# Power_Regulators_Digital_3.net
KiCad netlist of a schematic drawn in Altium Designer
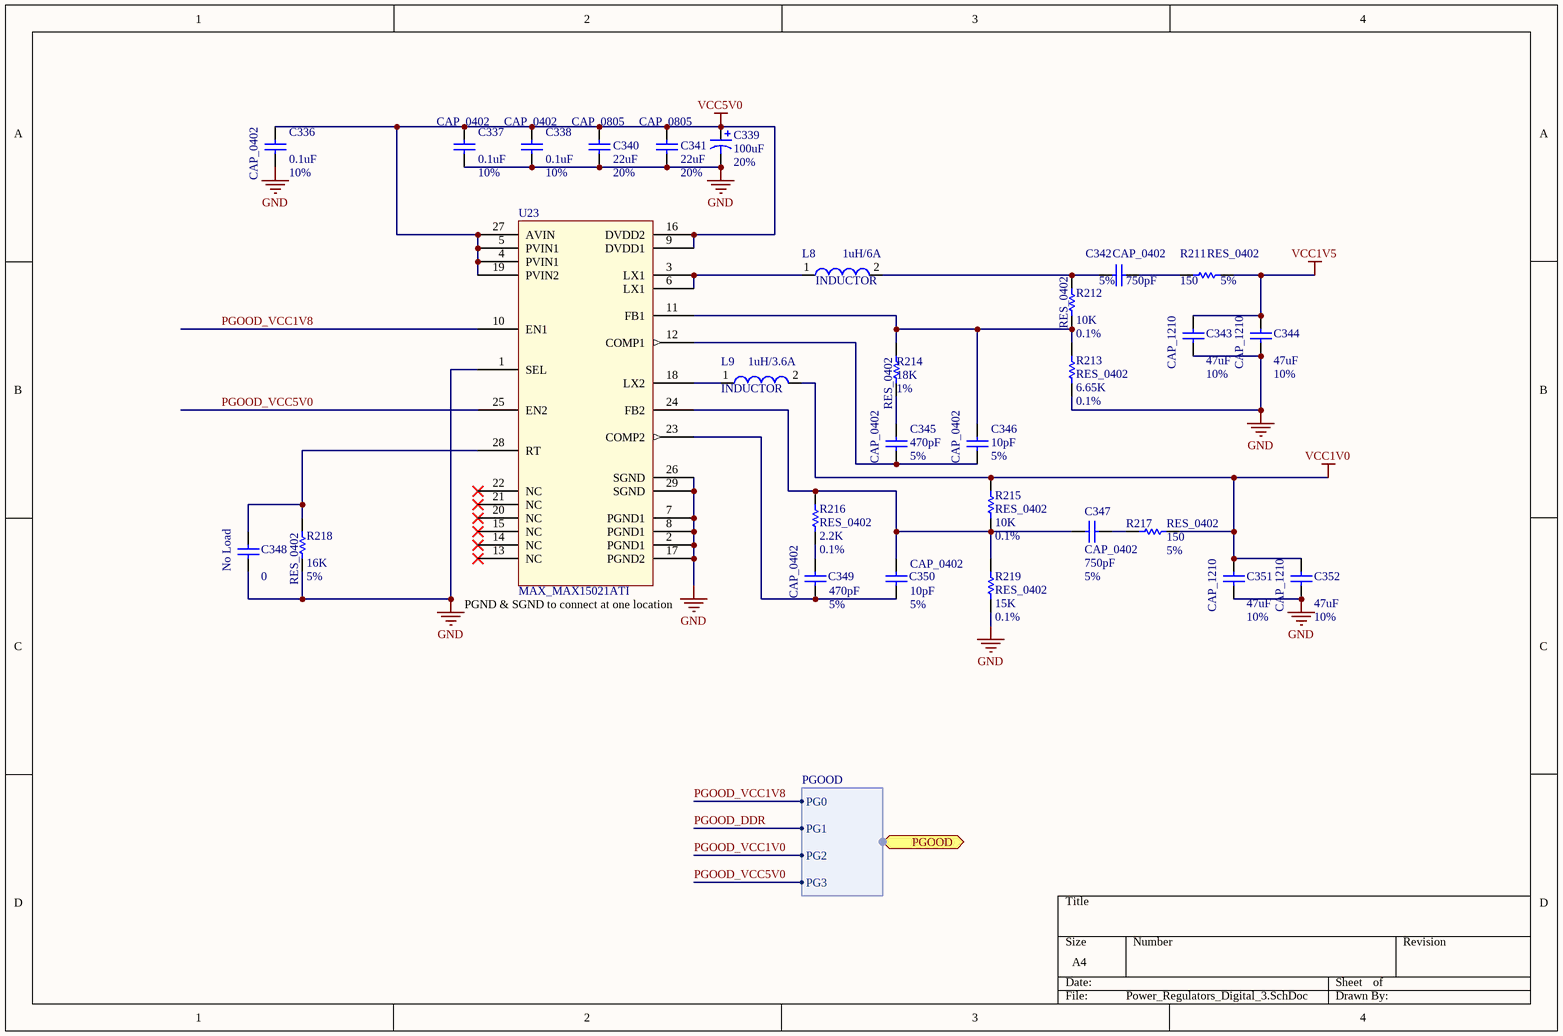
[diagram p0: Power_Regulators_Digital_3.SchDoc]

(export (version "E")
  (design (tool "Eeschema 10.0.6"))
  (components
    (comp (ref "C336")
      (value "CAP_0402")
      (footprint "CAPC0402(1005)60_N")
      (description "0.1uf, ceramic, 10%, 6.3V, X5R, 0402")
      (fields
        (field (name "ALTIUM_VALUE") "0.1uF")
        (field (name "TOLERANCE") "10%")
        (field (name "PART NUMBER") "C1005X5R0J104K")
        (field (name "MANUFACTURER") "TDK Corporation")
      )
      (libsource (lib "COMRAD_Database") (part "CAP_0402"))
    )
    (comp (ref "C337")
      (value "CAP_0402")
      (footprint "CAPC0402(1005)60_N")
      (description "0.1uf, ceramic, 10%, 6.3V, X5R, 0402")
      (fields
        (field (name "ALTIUM_VALUE") "0.1uF")
        (field (name "TOLERANCE") "10%")
        (field (name "PART NUMBER") "C1005X5R0J104K")
        (field (name "MANUFACTURER") "TDK Corporation")
      )
      (libsource (lib "COMRAD_Database") (part "CAP_0402"))
    )
    (comp (ref "C338")
      (value "CAP_0402")
      (footprint "CAPC0402(1005)60_N")
      (description "0.1uf, ceramic, 10%, 6.3V, X5R, 0402")
      (fields
        (field (name "ALTIUM_VALUE") "0.1uF")
        (field (name "TOLERANCE") "10%")
        (field (name "PART NUMBER") "C1005X5R0J104K")
        (field (name "MANUFACTURER") "TDK Corporation")
      )
      (libsource (lib "COMRAD_Database") (part "CAP_0402"))
    )
    (comp (ref "C339")
      (value "100uF")
      (footprint "Polarized_CAPC1210(3225)")
      (description "100uF, tantalum, 20% 10V, 1210")
      (fields
        (field (name "TOLERANCE") "20%")
        (field (name "PART NUMBER") "TLCT107M010XTA")
        (field (name "MANUFACTURER") "AVX Corporation")
      )
      (libsource (lib "COMRAD_Database") (part "Cap Pol1"))
    )
    (comp (ref "C340")
      (value "CAP_0805")
      (footprint "CAPC0805(2012)75_N")
      (description "22uF, ceramic, 20%, 6.3V, X5R, 0805")
      (fields
        (field (name "ALTIUM_VALUE") "22uF")
        (field (name "TOLERANCE") "20%")
        (field (name "PART NUMBER") "JMK212BJ226MG-T")
        (field (name "MANUFACTURER") "Taiyo Yuden")
      )
      (libsource (lib "COMRAD_Database") (part "CAP_0805"))
    )
    (comp (ref "C341")
      (value "CAP_0805")
      (footprint "CAPC0805(2012)75_N")
      (description "22uF, ceramic, 20%, 6.3V, X5R, 0805")
      (fields
        (field (name "ALTIUM_VALUE") "22uF")
        (field (name "TOLERANCE") "20%")
        (field (name "PART NUMBER") "JMK212BJ226MG-T")
        (field (name "MANUFACTURER") "Taiyo Yuden")
      )
      (libsource (lib "COMRAD_Database") (part "CAP_0805"))
    )
    (comp (ref "C342")
      (value "CAP_0402")
      (footprint "CAPC0402(1005)60_N")
      (description "750pF, ceramic, 5% 25V NP0, 0402")
      (fields
        (field (name "ALTIUM_VALUE") "750pF")
        (field (name "TOLERANCE") "5%")
        (field (name "PART NUMBER") "C0402C751J3GACTU")
        (field (name "MANUFACTURER") "Kemet")
      )
      (libsource (lib "COMRAD_Database") (part "CAP_0402"))
    )
    (comp (ref "C343")
      (value "CAP_1210")
      (footprint "CAPC1210(3225)100_N")
      (description "47uF, ceramic 10% 10V, X5R, 1210")
      (fields
        (field (name "ALTIUM_VALUE") "47uF")
        (field (name "TOLERANCE") "10%")
        (field (name "PART NUMBER") "GRM32ER61A476KE20L")
        (field (name "MANUFACTURER") "Murata Electronics North America")
      )
      (libsource (lib "COMRAD_Database") (part "CAP_1210"))
    )
    (comp (ref "C344")
      (value "CAP_1210")
      (footprint "CAPC1210(3225)100_N")
      (description "47uF, ceramic 10% 10V, X5R, 1210")
      (fields
        (field (name "ALTIUM_VALUE") "47uF")
        (field (name "TOLERANCE") "10%")
        (field (name "PART NUMBER") "GRM32ER61A476KE20L")
        (field (name "MANUFACTURER") "Murata Electronics North America")
      )
      (libsource (lib "COMRAD_Database") (part "CAP_1210"))
    )
    (comp (ref "C345")
      (value "CAP_0402")
      (footprint "CAPC0402(1005)60_N")
      (description "470pF, ceramic, 5%, 25V, X7R, 0402")
      (fields
        (field (name "ALTIUM_VALUE") "470pF")
        (field (name "TOLERANCE") "5%")
        (field (name "PART NUMBER") "ECJ-0EB1E471K")
        (field (name "MANUFACTURER") "Panasonic-ECG")
      )
      (libsource (lib "COMRAD_Database") (part "CAP_0402"))
    )
    (comp (ref "C346")
      (value "CAP_0402")
      (footprint "CAPC0402(1005)60_N")
      (description "10pF, ceramic, 5%, 50V, NP0, 0402")
      (fields
        (field (name "ALTIUM_VALUE") "10pF")
        (field (name "TOLERANCE") "5%")
        (field (name "PART NUMBER") "VJ0402A100JXACW1BC")
        (field (name "MANUFACTURER") "BC COMPONENTS")
      )
      (libsource (lib "COMRAD_Database") (part "CAP_0402"))
    )
    (comp (ref "C347")
      (value "CAP_0402")
      (footprint "CAPC0402(1005)60_N")
      (description "750pF, ceramic, 5% 25V NP0, 0402")
      (fields
        (field (name "ALTIUM_VALUE") "750pF")
        (field (name "TOLERANCE") "5%")
        (field (name "PART NUMBER") "C0402C751J3GACTU")
        (field (name "MANUFACTURER") "Kemet")
      )
      (libsource (lib "COMRAD_Database") (part "CAP_0402"))
    )
    (comp (ref "C348")
      (value "0")
      (footprint "CAPC0201(0603)33_N:CAPC0201(0603)33_N")
      (description "Generic Capacitor")
      (fields
        (field (name "PART NUMBER") "No Load_0")
        (field (name "MANUFACTURER") "No Load")
        (field (name "Comment") "CAP_0201")
      )
      (libsource (lib "COMRAD_Database") (part "CAP_0201"))
    )
    (comp (ref "C349")
      (value "CAP_0402")
      (footprint "CAPC0402(1005)60_N")
      (description "470pF, ceramic, 5%, 25V, X7R, 0402")
      (fields
        (field (name "ALTIUM_VALUE") "470pF")
        (field (name "TOLERANCE") "5%")
        (field (name "PART NUMBER") "ECJ-0EB1E471K")
        (field (name "MANUFACTURER") "Panasonic-ECG")
      )
      (libsource (lib "COMRAD_Database") (part "CAP_0402"))
    )
    (comp (ref "C350")
      (value "CAP_0402")
      (footprint "CAPC0402(1005)60_N")
      (description "10pF, ceramic, 5%, 50V, NP0, 0402")
      (fields
        (field (name "ALTIUM_VALUE") "10pF")
        (field (name "TOLERANCE") "5%")
        (field (name "PART NUMBER") "VJ0402A100JXACW1BC")
        (field (name "MANUFACTURER") "BC COMPONENTS")
      )
      (libsource (lib "COMRAD_Database") (part "CAP_0402"))
    )
    (comp (ref "C351")
      (value "CAP_1210")
      (footprint "CAPC1210(3225)100_N")
      (description "47uF, ceramic 10% 10V, X5R, 1210")
      (fields
        (field (name "ALTIUM_VALUE") "47uF")
        (field (name "TOLERANCE") "10%")
        (field (name "PART NUMBER") "GRM32ER61A476KE20L")
        (field (name "MANUFACTURER") "Murata Electronics North America")
      )
      (libsource (lib "COMRAD_Database") (part "CAP_1210"))
    )
    (comp (ref "C352")
      (value "CAP_1210")
      (footprint "CAPC1210(3225)100_N")
      (description "47uF, ceramic 10% 10V, X5R, 1210")
      (fields
        (field (name "ALTIUM_VALUE") "47uF")
        (field (name "TOLERANCE") "10%")
        (field (name "PART NUMBER") "GRM32ER61A476KE20L")
        (field (name "MANUFACTURER") "Murata Electronics North America")
      )
      (libsource (lib "COMRAD_Database") (part "CAP_1210"))
    )
    (comp (ref "L8")
      (value "INDUCTOR")
      (footprint "Inductor_SRN6045-Series_2-PIN")
      (description "SRN6045-1R0Y, 1uH 4.2A-8.5A, CDRH6D38")
      (fields
        (field (name "ALTIUM_VALUE") "1uH/6A")
        (field (name "PART NUMBER") "SRN6045-1R0Y")
        (field (name "MANUFACTURER") "Bourns")
      )
      (libsource (lib "COMRAD_Database") (part "INDUCTOR"))
    )
    (comp (ref "L9")
      (value "INDUCTOR")
      (footprint "Inductor_NRS5020T1R0NMGJ_2-PIN")
      (description "NRS5020T1R0NMGJ, 1uH 3.6A, 5020")
      (fields
        (field (name "ALTIUM_VALUE") "1uH/3.6A")
        (field (name "PART NUMBER") "NRS5020T1R0NMGJ")
        (field (name "MANUFACTURER") "Taiyo Yuden")
      )
      (libsource (lib "COMRAD_Database") (part "INDUCTOR"))
    )
    (comp (ref "R211")
      (value "RES_0402")
      (footprint "RESC0402(1005)_N")
      (description "150 ohm, 5% 1/16W, 0402")
      (fields
        (field (name "ALTIUM_VALUE") "150")
        (field (name "TOLERANCE") "5%")
        (field (name "PART NUMBER") "RC0402JR-07150RL")
        (field (name "MANUFACTURER") "Yageo America")
      )
      (libsource (lib "COMRAD_Database") (part "RES_0402"))
    )
    (comp (ref "R212")
      (value "RES_0402")
      (footprint "RESC0402(1005)_N")
      (description "10K ohm, 0.1% 1/16W, 0402")
      (fields
        (field (name "ALTIUM_VALUE") "10K")
        (field (name "TOLERANCE") "0.1%")
        (field (name "PART NUMBER") "ERA-2AEB103X")
        (field (name "MANUFACTURER") "Panasonic - ECG")
      )
      (libsource (lib "COMRAD_Database") (part "RES_0402"))
    )
    (comp (ref "R213")
      (value "RES_0402")
      (footprint "RESC0402(1005)_N")
      (description "6.65K ohm, 0.1% 1/16W, 0402")
      (fields
        (field (name "ALTIUM_VALUE") "6.65K")
        (field (name "TOLERANCE") "0.1%")
        (field (name "PART NUMBER") "2-1879215-2")
        (field (name "MANUFACTURER") "TE Connectivity")
      )
      (libsource (lib "COMRAD_Database") (part "RES_0402"))
    )
    (comp (ref "R214")
      (value "RES_0402")
      (footprint "RESC0402(1005)_N")
      (description "18K ohm, 1% 1/16W, 0402")
      (fields
        (field (name "ALTIUM_VALUE") "18K")
        (field (name "TOLERANCE") "1%")
        (field (name "PART NUMBER") "MCR01MZPF1802")
        (field (name "MANUFACTURER") "ROHM")
      )
      (libsource (lib "COMRAD_Database") (part "RES_0402"))
    )
    (comp (ref "R215")
      (value "RES_0402")
      (footprint "RESC0402(1005)_N")
      (description "10K ohm, 0.1% 1/16W, 0402")
      (fields
        (field (name "ALTIUM_VALUE") "10K")
        (field (name "TOLERANCE") "0.1%")
        (field (name "PART NUMBER") "ERA-2AEB103X")
        (field (name "MANUFACTURER") "Panasonic - ECG")
      )
      (libsource (lib "COMRAD_Database") (part "RES_0402"))
    )
    (comp (ref "R216")
      (value "RES_0402")
      (footprint "RESC0402(1005)_N")
      (description "2.2K ohm, 0.1% 1/16W, 0402")
      (fields
        (field (name "ALTIUM_VALUE") "2.2K")
        (field (name "TOLERANCE") "0.1%")
        (field (name "PART NUMBER") "ERA-2AEB222X")
        (field (name "MANUFACTURER") "Panasonic - ECG")
      )
      (libsource (lib "COMRAD_Database") (part "RES_0402"))
    )
    (comp (ref "R217")
      (value "RES_0402")
      (footprint "RESC0402(1005)_N")
      (description "150 ohm, 5% 1/16W, 0402")
      (fields
        (field (name "ALTIUM_VALUE") "150")
        (field (name "TOLERANCE") "5%")
        (field (name "PART NUMBER") "RC0402JR-07150RL")
        (field (name "MANUFACTURER") "Yageo America")
      )
      (libsource (lib "COMRAD_Database") (part "RES_0402"))
    )
    (comp (ref "R218")
      (value "RES_0402")
      (footprint "RESC0402(1005)_N")
      (description "16K ohm, 5% 1/16W, 0402")
      (fields
        (field (name "ALTIUM_VALUE") "16K")
        (field (name "TOLERANCE") "5%")
        (field (name "PART NUMBER") "CRCW040216K0JNED")
        (field (name "MANUFACTURER") "Vishay/Dale")
      )
      (libsource (lib "COMRAD_Database") (part "RES_0402"))
    )
    (comp (ref "R219")
      (value "RES_0402")
      (footprint "RESC0402(1005)_N")
      (description "15K ohm, 0.1% 1/16W, 0402")
      (fields
        (field (name "ALTIUM_VALUE") "15K")
        (field (name "TOLERANCE") "0.1%")
        (field (name "PART NUMBER") "ERA-2AEB153X")
        (field (name "MANUFACTURER") "Panasonic - ECG")
      )
      (libsource (lib "COMRAD_Database") (part "RES_0402"))
    )
    (comp (ref "U23")
      (value "MAX_MAX15021ATI")
      (footprint "MAX_MAX15021ATI_28TQFN_T2855-6")
      (description "MAX15021ATI, 4A/2A, 4MHz, Step-Down DC-DC Regulator, TQFN28")
      (fields
        (field (name "PART NUMBER") "MAX15021ATI+")
        (field (name "MANUFACTURER") "Maxim Integrated Products")
      )
      (libsource (lib "COMRAD_Database") (part "MAX_MAX15021ATI"))
    )
  )
  (nets
    (net (code "4") (name "/PGOOD_VCC1V8") (class "Default")
      (node (ref "U23") (pin "10") (pinfunction "EN1_10") (pintype "power_in"))
    )
    (net (code "5") (name "/PGOOD_VCC5V0") (class "Default")
      (node (ref "U23") (pin "25") (pinfunction "EN2_25") (pintype "power_in"))
    )
    (net (code "7") (name "GND") (class "Default")
      (node (ref "C336") (pin "1") (pinfunction "1_1") (pintype "passive"))
      (node (ref "C337") (pin "1") (pinfunction "1_1") (pintype "passive"))
      (node (ref "C338") (pin "1") (pinfunction "1_1") (pintype "passive"))
      (node (ref "C339") (pin "2") (pinfunction "2_2") (pintype "passive"))
      (node (ref "C340") (pin "1") (pinfunction "1_1") (pintype "passive"))
      (node (ref "C341") (pin "1") (pinfunction "1_1") (pintype "passive"))
      (node (ref "C343") (pin "1") (pinfunction "1_1") (pintype "passive"))
      (node (ref "C344") (pin "1") (pinfunction "1_1") (pintype "passive"))
      (node (ref "C348") (pin "1") (pinfunction "1_1") (pintype "passive"))
      (node (ref "C351") (pin "1") (pinfunction "1_1") (pintype "passive"))
      (node (ref "C352") (pin "1") (pinfunction "1_1") (pintype "passive"))
      (node (ref "R213") (pin "1") (pinfunction "1_1") (pintype "passive"))
      (node (ref "R218") (pin "2") (pinfunction "2_2") (pintype "passive"))
      (node (ref "R219") (pin "1") (pinfunction "1_1") (pintype "passive"))
      (node (ref "U23") (pin "1") (pinfunction "SEL_1") (pintype "power_in"))
      (node (ref "U23") (pin "17") (pinfunction "PGND2_17") (pintype "power_in"))
      (node (ref "U23") (pin "2") (pinfunction "PGND1_2") (pintype "power_in"))
      (node (ref "U23") (pin "26") (pinfunction "SGND_26") (pintype "power_in"))
      (node (ref "U23") (pin "29") (pinfunction "SGND_29") (pintype "power_in"))
      (node (ref "U23") (pin "7") (pinfunction "PGND1_7") (pintype "power_in"))
      (node (ref "U23") (pin "8") (pinfunction "PGND1_8") (pintype "power_in"))
    )
    (net (code "8") (name "Net-(C342-Pad1)") (class "Default")
      (node (ref "C342") (pin "1") (pinfunction "1_1") (pintype "passive"))
      (node (ref "L8") (pin "2") (pinfunction "2_2") (pintype "passive"))
      (node (ref "R212") (pin "2") (pinfunction "2_2") (pintype "passive"))
    )
    (net (code "9") (name "Net-(C342-Pad2)") (class "Default")
      (node (ref "C342") (pin "2") (pinfunction "2_2") (pintype "passive"))
      (node (ref "R211") (pin "1") (pinfunction "1_1") (pintype "passive"))
    )
    (net (code "10") (name "Net-(C345-Pad2)") (class "Default")
      (node (ref "C345") (pin "2") (pinfunction "2_2") (pintype "passive"))
      (node (ref "R214") (pin "1") (pinfunction "1_1") (pintype "passive"))
    )
    (net (code "11") (name "Net-(C347-Pad2)") (class "Default")
      (node (ref "C347") (pin "2") (pinfunction "2_2") (pintype "passive"))
      (node (ref "R217") (pin "1") (pinfunction "1_1") (pintype "passive"))
    )
    (net (code "12") (name "Net-(C349-Pad2)") (class "Default")
      (node (ref "C349") (pin "2") (pinfunction "2_2") (pintype "passive"))
      (node (ref "R216") (pin "1") (pinfunction "1_1") (pintype "passive"))
    )
    (net (code "13") (name "Net-(L8-Pad1)") (class "Default")
      (node (ref "L8") (pin "1") (pinfunction "1_1") (pintype "passive"))
      (node (ref "U23") (pin "3") (pinfunction "LX1_3") (pintype "power_in"))
      (node (ref "U23") (pin "6") (pinfunction "LX1_6") (pintype "power_in"))
    )
    (net (code "14") (name "Net-(U23-COMP1)") (class "Default")
      (node (ref "C345") (pin "1") (pinfunction "1_1") (pintype "passive"))
      (node (ref "C346") (pin "1") (pinfunction "1_1") (pintype "passive"))
      (node (ref "U23") (pin "12") (pinfunction "COMP1_12") (pintype "output"))
    )
    (net (code "15") (name "Net-(U23-COMP2)") (class "Default")
      (node (ref "C349") (pin "1") (pinfunction "1_1") (pintype "passive"))
      (node (ref "C350") (pin "1") (pinfunction "1_1") (pintype "passive"))
      (node (ref "U23") (pin "23") (pinfunction "COMP2_23") (pintype "output"))
    )
    (net (code "16") (name "Net-(U23-FB1)") (class "Default")
      (node (ref "C346") (pin "2") (pinfunction "2_2") (pintype "passive"))
      (node (ref "R212") (pin "1") (pinfunction "1_1") (pintype "passive"))
      (node (ref "R213") (pin "2") (pinfunction "2_2") (pintype "passive"))
      (node (ref "R214") (pin "2") (pinfunction "2_2") (pintype "passive"))
      (node (ref "U23") (pin "11") (pinfunction "FB1_11") (pintype "power_in"))
    )
    (net (code "17") (name "Net-(U23-FB2)") (class "Default")
      (node (ref "C347") (pin "1") (pinfunction "1_1") (pintype "passive"))
      (node (ref "C350") (pin "2") (pinfunction "2_2") (pintype "passive"))
      (node (ref "R215") (pin "1") (pinfunction "1_1") (pintype "passive"))
      (node (ref "R216") (pin "2") (pinfunction "2_2") (pintype "passive"))
      (node (ref "R219") (pin "2") (pinfunction "2_2") (pintype "passive"))
      (node (ref "U23") (pin "24") (pinfunction "FB2_24") (pintype "power_in"))
    )
    (net (code "18") (name "Net-(U23-LX2)") (class "Default")
      (node (ref "L9") (pin "1") (pinfunction "1_1") (pintype "passive"))
      (node (ref "U23") (pin "18") (pinfunction "LX2_18") (pintype "power_in"))
    )
    (net (code "19") (name "Net-(U23-RT)") (class "Default")
      (node (ref "C348") (pin "2") (pinfunction "2_2") (pintype "passive"))
      (node (ref "R218") (pin "1") (pinfunction "1_1") (pintype "passive"))
      (node (ref "U23") (pin "28") (pinfunction "RT_28") (pintype "power_in"))
    )
    (net (code "20") (name "VCC1V0") (class "Default")
      (node (ref "C351") (pin "2") (pinfunction "2_2") (pintype "passive"))
      (node (ref "C352") (pin "2") (pinfunction "2_2") (pintype "passive"))
      (node (ref "L9") (pin "2") (pinfunction "2_2") (pintype "passive"))
      (node (ref "R215") (pin "2") (pinfunction "2_2") (pintype "passive"))
      (node (ref "R217") (pin "2") (pinfunction "2_2") (pintype "passive"))
    )
    (net (code "21") (name "VCC1V5") (class "Default")
      (node (ref "C343") (pin "2") (pinfunction "2_2") (pintype "passive"))
      (node (ref "C344") (pin "2") (pinfunction "2_2") (pintype "passive"))
      (node (ref "R211") (pin "2") (pinfunction "2_2") (pintype "passive"))
    )
    (net (code "22") (name "VCC5V0") (class "Default")
      (node (ref "C336") (pin "2") (pinfunction "2_2") (pintype "passive"))
      (node (ref "C337") (pin "2") (pinfunction "2_2") (pintype "passive"))
      (node (ref "C338") (pin "2") (pinfunction "2_2") (pintype "passive"))
      (node (ref "C339") (pin "1") (pinfunction "1_1") (pintype "passive"))
      (node (ref "C340") (pin "2") (pinfunction "2_2") (pintype "passive"))
      (node (ref "C341") (pin "2") (pinfunction "2_2") (pintype "passive"))
      (node (ref "U23") (pin "16") (pinfunction "DVDD2_16") (pintype "power_in"))
      (node (ref "U23") (pin "19") (pinfunction "PVIN2_19") (pintype "power_in"))
      (node (ref "U23") (pin "27") (pinfunction "AVIN_27") (pintype "power_in"))
      (node (ref "U23") (pin "4") (pinfunction "PVIN1_4") (pintype "power_in"))
      (node (ref "U23") (pin "5") (pinfunction "PVIN1_5") (pintype "power_in"))
      (node (ref "U23") (pin "9") (pinfunction "DVDD1_9") (pintype "power_in"))
    )
    (net (code "23") (name "unconnected-(U23-NC-Pad13)") (class "Default")
      (node (ref "U23") (pin "13") (pinfunction "NC_13") (pintype "power_in+no_connect"))
    )
    (net (code "24") (name "unconnected-(U23-NC-Pad14)") (class "Default")
      (node (ref "U23") (pin "14") (pinfunction "NC_14") (pintype "power_in+no_connect"))
    )
    (net (code "25") (name "unconnected-(U23-NC-Pad15)") (class "Default")
      (node (ref "U23") (pin "15") (pinfunction "NC_15") (pintype "power_in+no_connect"))
    )
    (net (code "26") (name "unconnected-(U23-NC-Pad20)") (class "Default")
      (node (ref "U23") (pin "20") (pinfunction "NC_20") (pintype "power_in+no_connect"))
    )
    (net (code "27") (name "unconnected-(U23-NC-Pad21)") (class "Default")
      (node (ref "U23") (pin "21") (pinfunction "NC_21") (pintype "power_in+no_connect"))
    )
    (net (code "28") (name "unconnected-(U23-NC-Pad22)") (class "Default")
      (node (ref "U23") (pin "22") (pinfunction "NC_22") (pintype "power_in+no_connect"))
    )
  )
)
